# Sheet1_xbreak-k.net
KiCad netlist of a schematic drawn in Altium Designer
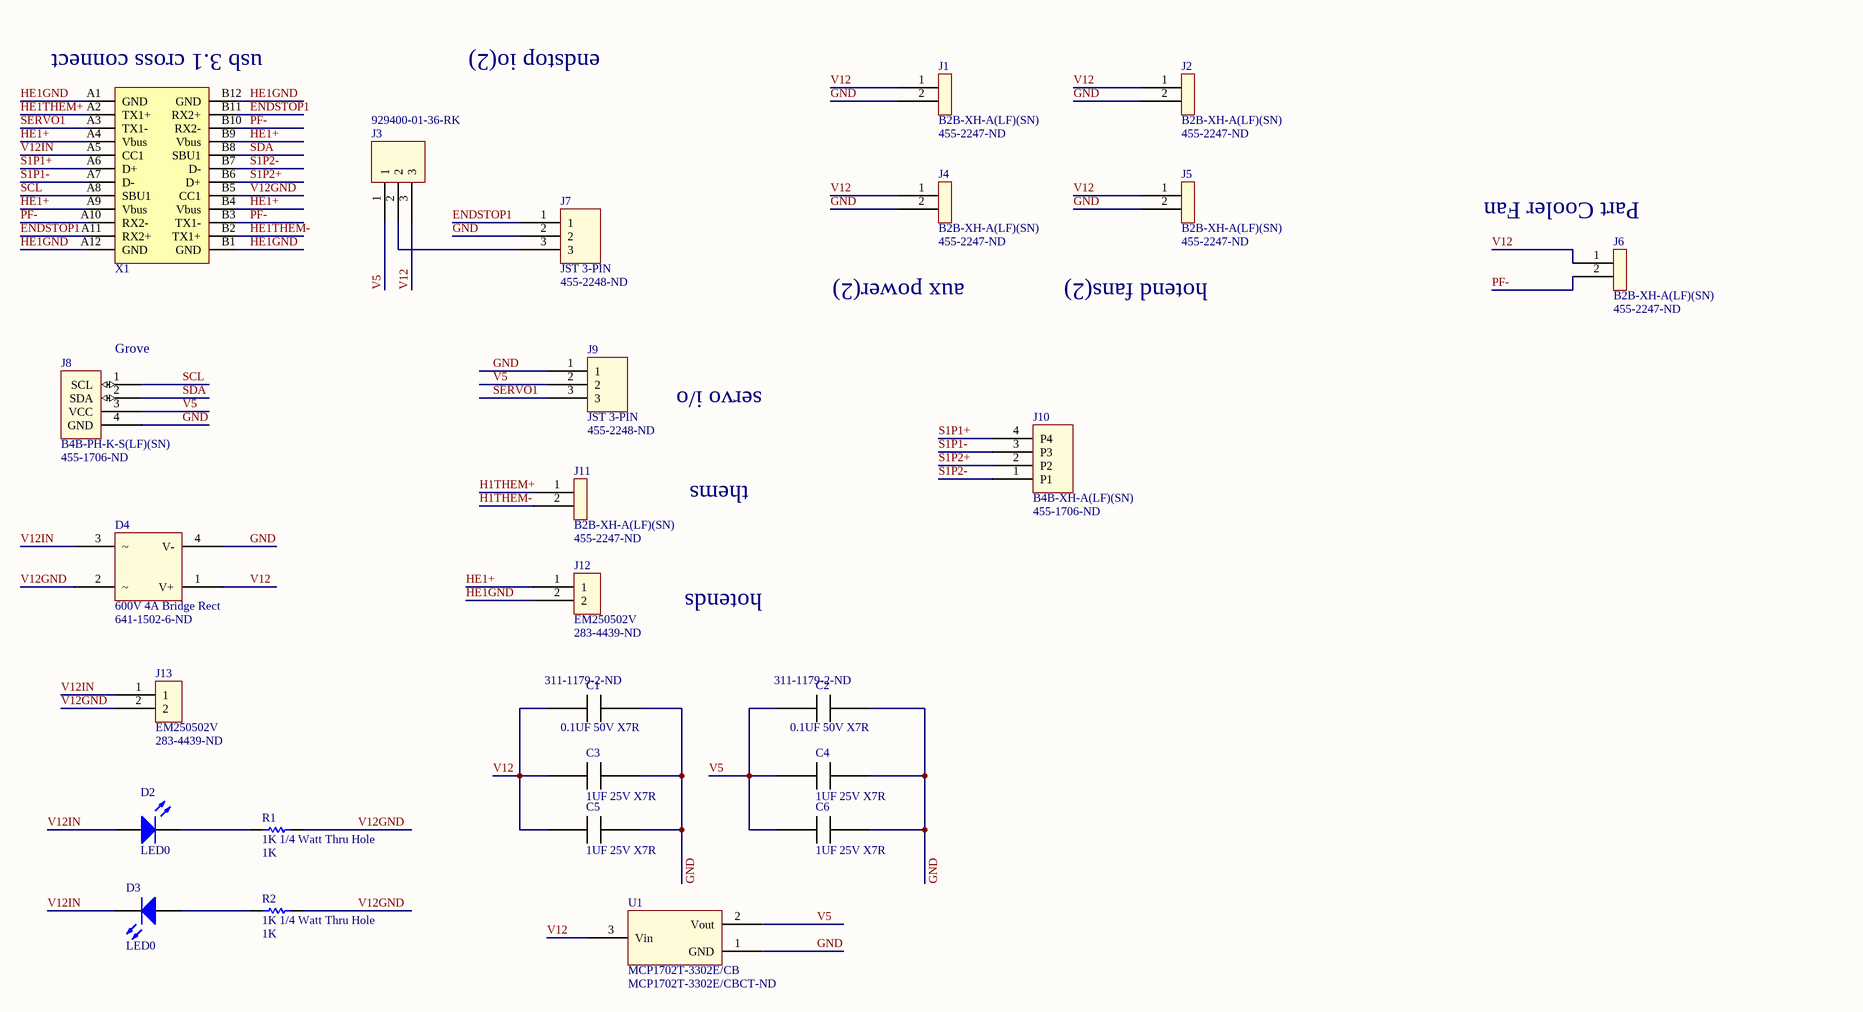
[diagram p0: Sheet1_xbreak-k.SchDoc]

(export (version "E")
  (design (tool "Eeschema 10.0.6"))
  (components
    (comp (ref "C1")
      (value "0.1UF 50V X7R")
      (footprint "C1206YageoX7R")
      (description "CAP CER 0.1UF 50V X7R 1206 YAGEO CC1206KRX7R9BB104")
      (fields (field (name "SUPPLIER PART NUMBER 1") "311-1179-2-ND"))
      (libsource (lib "servo") (part "CC1206KRX7R9BB104"))
    )
    (comp (ref "C2")
      (value "0.1UF 50V X7R")
      (footprint "C1206YageoX7R")
      (description "CAP CER 0.1UF 50V X7R 1206 YAGEO CC1206KRX7R9BB104")
      (fields (field (name "SUPPLIER PART NUMBER 1") "311-1179-2-ND"))
      (libsource (lib "servo") (part "CC1206KRX7R9BB104"))
    )
    (comp (ref "C3")
      (value "1UF 25V X7R")
      (footprint "C1206YageoX7R")
      (description "CAP CER 1UF 25V X7R 1206 Yageo CC1206KKX7R8BB105")
      (libsource (lib "servo") (part "CC1206KKX7R8BB105"))
    )
    (comp (ref "C4")
      (value "1UF 25V X7R")
      (footprint "C1206YageoX7R")
      (description "CAP CER 1UF 25V X7R 1206 Yageo CC1206KKX7R8BB105")
      (libsource (lib "servo") (part "CC1206KKX7R8BB105"))
    )
    (comp (ref "C5")
      (value "1UF 25V X7R")
      (footprint "C1206YageoX7R")
      (description "CAP CER 1UF 25V X7R 1206 Yageo CC1206KKX7R8BB105")
      (libsource (lib "servo") (part "CC1206KKX7R8BB105"))
    )
    (comp (ref "C6")
      (value "1UF 25V X7R")
      (footprint "C1206YageoX7R")
      (description "CAP CER 1UF 25V X7R 1206 Yageo CC1206KKX7R8BB105")
      (libsource (lib "servo") (part "CC1206KKX7R8BB105"))
    )
    (comp (ref "D2")
      (value "LED0")
      (footprint "LED-0")
      (description "Typical INFRARED GaAs LED")
      (fields (field (name "PUBLISHER") "Altium Limited"))
      (libsource (lib "Miscellaneous Devices") (part "LED0"))
    )
    (comp (ref "D3")
      (value "LED0")
      (footprint "LED-0")
      (description "Typical INFRARED GaAs LED")
      (fields (field (name "PUBLISHER") "Altium Limited"))
      (libsource (lib "Miscellaneous Devices") (part "LED0"))
    )
    (comp (ref "D4")
      (value "600V 4A Bridge Rect")
      (footprint "Z4DGP406L-HF")
      (description "RECT BRIDGE GP 600V 4A Z4-D ComChip Z4DGP406L-HF")
      (fields (field (name "SUPPLIER PART NUMBER 1") "641-1502-6-ND"))
      (libsource (lib "xbreak") (part "Z4DGP406L-HF"))
    )
    (comp (ref "J1")
      (value "B2B-XH-A(LF)(SN)")
      (footprint "77311-118-02LF")
      (description "CONN HEADER XH TOP 2POS 2.5MM  JST B2B-XH-A(LF)(SN)")
      (fields (field (name "SUPPLIER PART NUMBER 1") "455-2247-ND"))
      (libsource (lib "xbreak") (part "B2B-XH-A(LF)(SN)"))
    )
    (comp (ref "J2")
      (value "B2B-XH-A(LF)(SN)")
      (footprint "77311-118-02LF")
      (description "CONN HEADER XH TOP 2POS 2.5MM  JST B2B-XH-A(LF)(SN)")
      (fields (field (name "SUPPLIER PART NUMBER 1") "455-2247-ND"))
      (libsource (lib "xbreak") (part "B2B-XH-A(LF)(SN)"))
    )
    (comp (ref "J3")
      (value "929400-01-36-RK")
      (footprint "929400-01-36-RK")
      (description "3M 929400-01-36-RK CONN HEADER .100 SNGL STR 36POS - Use 3 Pin")
      (libsource (lib "xbreak") (part "929400-01-36-RK"))
    )
    (comp (ref "J4")
      (value "B2B-XH-A(LF)(SN)")
      (footprint "77311-118-02LF")
      (description "CONN HEADER XH TOP 2POS 2.5MM  JST B2B-XH-A(LF)(SN)")
      (fields (field (name "SUPPLIER PART NUMBER 1") "455-2247-ND"))
      (libsource (lib "xbreak") (part "B2B-XH-A(LF)(SN)"))
    )
    (comp (ref "J5")
      (value "B2B-XH-A(LF)(SN)")
      (footprint "77311-118-02LF")
      (description "CONN HEADER XH TOP 2POS 2.5MM  JST B2B-XH-A(LF)(SN)")
      (fields (field (name "SUPPLIER PART NUMBER 1") "455-2247-ND"))
      (libsource (lib "xbreak") (part "B2B-XH-A(LF)(SN)"))
    )
    (comp (ref "J6")
      (value "B2B-XH-A(LF)(SN)")
      (footprint "77311-118-02LF")
      (description "CONN HEADER XH TOP 2POS 2.5MM  JST B2B-XH-A(LF)(SN)")
      (fields (field (name "SUPPLIER PART NUMBER 1") "455-2247-ND"))
      (libsource (lib "xbreak") (part "B2B-XH-A(LF)(SN)"))
    )
    (comp (ref "J7")
      (value "JST 3-PIN")
      (footprint "B3B-XH-A(LF)(SN)")
      (description "CONN HEADER XH TOP 3POS 2.5MM JST B3B-XH-A(LF)(SN)")
      (fields (field (name "SUPPLIER PART NUMBER 1") "455-2248-ND"))
      (libsource (lib "xbreak") (part "B3B-XH-A(LF)(SN)"))
    )
    (comp (ref "J8")
      (value "B4B-PH-K-S(LF)(SN)")
      (footprint "B4B-PH-K-S(LF)(SN)")
      (fields (field (name "SUPPLIER PART NUMBER 1") "455-1706-ND"))
      (libsource (lib "servo") (part "B4B-PH-K-S(LF)(SN)"))
    )
    (comp (ref "J9")
      (value "JST 3-PIN")
      (footprint "B3B-XH-A(LF)(SN)")
      (description "CONN HEADER XH TOP 3POS 2.5MM JST B3B-XH-A(LF)(SN)")
      (fields (field (name "SUPPLIER PART NUMBER 1") "455-2248-ND"))
      (libsource (lib "xbreak") (part "B3B-XH-A(LF)(SN)"))
    )
    (comp (ref "J10")
      (value "B4B-XH-A(LF)(SN)")
      (footprint "B4B-PH-K-S(LF)(SN)")
      (description "CONN HEADER XH TOP 4POS 2.5MM JST B4B-XH-A(LF)(SN)")
      (fields (field (name "SUPPLIER PART NUMBER 1") "455-1706-ND"))
      (libsource (lib "xbreak") (part "B4B-XH-A(LF)(SN)"))
    )
    (comp (ref "J11")
      (value "B2B-XH-A(LF)(SN)")
      (footprint "77311-118-02LF")
      (description "CONN HEADER XH TOP 2POS 2.5MM  JST B2B-XH-A(LF)(SN)")
      (fields (field (name "SUPPLIER PART NUMBER 1") "455-2247-ND"))
      (libsource (lib "xbreak") (part "B2B-XH-A(LF)(SN)"))
    )
    (comp (ref "J12")
      (value "EM250502V")
      (footprint "EM250502V")
      (description "TERM BLOCK 16A 300V 12-26AWG Eaton Bussman EM250502V")
      (fields (field (name "SUPPLIER PART NUMBER 1") "283-4439-ND"))
      (libsource (lib "xbreak") (part "EM250502V"))
    )
    (comp (ref "J13")
      (value "EM250502V")
      (footprint "EM250502V")
      (description "TERM BLOCK 16A 300V 12-26AWG Eaton Bussman EM250502V")
      (fields (field (name "SUPPLIER PART NUMBER 1") "283-4439-ND"))
      (libsource (lib "xbreak") (part "EM250502V"))
    )
    (comp (ref "R1")
      (value "1K 1/4 Watt Thru Hole")
      (footprint "AXIAL-0.3")
      (description "Resistor")
      (fields (field (name "ALTIUM_VALUE") "1K") (field (name "PUBLISHER") "Altium Limited"))
      (libsource (lib "Miscellaneous Devices") (part "Res1"))
    )
    (comp (ref "R2")
      (value "1K 1/4 Watt Thru Hole")
      (footprint "AXIAL-0.3")
      (description "Resistor")
      (fields (field (name "ALTIUM_VALUE") "1K") (field (name "PUBLISHER") "Altium Limited"))
      (libsource (lib "Miscellaneous Devices") (part "Res1"))
    )
    (comp (ref "U1")
      (value "MCP1702T-3302E/CB")
      (footprint "MCP1702-SOT-23A")
      (description "IC REG LDO 3.3V 0.25A SOT23A-3 Microchip MCP1702T-3302E/CB")
      (fields (field (name "SUPPLIER PART NUMBER 1") "MCP1702T-3302E/CBCT-ND"))
      (libsource (lib "servo") (part "MCP1702"))
    )
    (comp (ref "X1")
      (value "USB_3_1")
      (footprint "USB_3.1")
      (description "USB 3.1 Connector")
      (fields
        (field (name "MANUFACTURER") "Amphenol Commercial Products")
        (field (name "MANUFACTURER PART NUMBER") "12401548E4#2A")
      )
      (libsource (lib "Schlib2") (part "USB 3.1"))
    )
  )
  (nets
    (net (code "1") (name "/ENDSTOP1") (class "Default")
      (node (ref "J7") (pin "1") (pinfunction "1_1") (pintype "passive"))
      (node (ref "X1") (pin "A11") (pinfunction "RX2+_A11") (pintype "passive"))
      (node (ref "X1") (pin "B11") (pinfunction "RX2+_B11") (pintype "passive"))
    )
    (net (code "2") (name "/GND") (class "Default")
      (node (ref "C1") (pin "2") (pintype "passive"))
      (node (ref "C2") (pin "2") (pintype "passive"))
      (node (ref "C3") (pin "2") (pintype "passive"))
      (node (ref "C4") (pin "2") (pintype "passive"))
      (node (ref "C5") (pin "2") (pintype "passive"))
      (node (ref "C6") (pin "2") (pintype "passive"))
      (node (ref "D4") (pin "4") (pinfunction "V-_4") (pintype "passive"))
      (node (ref "J1") (pin "2") (pintype "passive"))
      (node (ref "J2") (pin "2") (pintype "passive"))
      (node (ref "J4") (pin "2") (pintype "passive"))
      (node (ref "J5") (pin "2") (pintype "passive"))
      (node (ref "J7") (pin "2") (pinfunction "2_2") (pintype "passive"))
      (node (ref "J8") (pin "4") (pinfunction "GND_4") (pintype "power_in"))
      (node (ref "J9") (pin "1") (pinfunction "1_1") (pintype "passive"))
      (node (ref "U1") (pin "1") (pinfunction "GND_1") (pintype "power_in"))
    )
    (net (code "3") (name "/H1THEM+") (class "Default") (node (ref "J11") (pin "1") (pintype "passive")))
    (net (code "4") (name "/H1THEM-") (class "Default") (node (ref "J11") (pin "2") (pintype "passive")))
    (net (code "5") (name "/HE1+") (class "Default")
      (node (ref "J12") (pin "1") (pinfunction "1_1") (pintype "passive"))
      (node (ref "X1") (pin "A4") (pinfunction "Vbus_A4") (pintype "passive"))
      (node (ref "X1") (pin "A9") (pinfunction "Vbus_A9") (pintype "passive"))
      (node (ref "X1") (pin "B4") (pinfunction "Vbus_B4") (pintype "passive"))
      (node (ref "X1") (pin "B9") (pinfunction "Vbus_B9") (pintype "passive"))
    )
    (net (code "6") (name "/HE1GND") (class "Default")
      (node (ref "J12") (pin "2") (pinfunction "2_2") (pintype "passive"))
      (node (ref "X1") (pin "A1") (pinfunction "GND_A1") (pintype "passive"))
      (node (ref "X1") (pin "A12") (pinfunction "GND_A12") (pintype "passive"))
      (node (ref "X1") (pin "B1") (pinfunction "GND_B1") (pintype "passive"))
      (node (ref "X1") (pin "B12") (pinfunction "GND_B12") (pintype "passive"))
    )
    (net (code "7") (name "/HE1THEM+") (class "Default")
      (node (ref "X1") (pin "A2") (pinfunction "TX1+_A2") (pintype "passive"))
    )
    (net (code "8") (name "/HE1THEM-") (class "Default")
      (node (ref "X1") (pin "B2") (pinfunction "TX1+_B2") (pintype "passive"))
    )
    (net (code "9") (name "/PF-") (class "Default")
      (node (ref "J6") (pin "2") (pintype "passive"))
      (node (ref "X1") (pin "A10") (pinfunction "RX2-_A10") (pintype "passive"))
      (node (ref "X1") (pin "B10") (pinfunction "RX2-_B10") (pintype "passive"))
      (node (ref "X1") (pin "B3") (pinfunction "TX1-_B3") (pintype "passive"))
    )
    (net (code "10") (name "/S1P1+") (class "Default")
      (node (ref "J10") (pin "4") (pinfunction "P4_4") (pintype "passive"))
      (node (ref "X1") (pin "A6") (pinfunction "D+_A6") (pintype "passive"))
    )
    (net (code "11") (name "/S1P1-") (class "Default")
      (node (ref "J10") (pin "3") (pinfunction "P3_3") (pintype "passive"))
      (node (ref "X1") (pin "A7") (pinfunction "D-_A7") (pintype "passive"))
    )
    (net (code "12") (name "/S1P2+") (class "Default")
      (node (ref "J10") (pin "2") (pinfunction "P2_2") (pintype "passive"))
      (node (ref "X1") (pin "B6") (pinfunction "D+_B6") (pintype "passive"))
    )
    (net (code "13") (name "/S1P2-") (class "Default")
      (node (ref "J10") (pin "1") (pinfunction "P1_1") (pintype "passive"))
      (node (ref "X1") (pin "B7") (pinfunction "D-_B7") (pintype "passive"))
    )
    (net (code "14") (name "/SCL") (class "Default")
      (node (ref "J8") (pin "1") (pinfunction "SCL_1") (pintype "bidirectional"))
      (node (ref "X1") (pin "A8") (pinfunction "SBU1_A8") (pintype "passive"))
    )
    (net (code "15") (name "/SDA") (class "Default")
      (node (ref "J8") (pin "2") (pinfunction "SDA_2") (pintype "bidirectional"))
      (node (ref "X1") (pin "B8") (pinfunction "SBU1_B8") (pintype "passive"))
    )
    (net (code "16") (name "/SERVO1") (class "Default")
      (node (ref "J9") (pin "3") (pinfunction "3_3") (pintype "passive"))
      (node (ref "X1") (pin "A3") (pinfunction "TX1-_A3") (pintype "passive"))
    )
    (net (code "17") (name "/V5") (class "Default")
      (node (ref "C2") (pin "1") (pintype "passive"))
      (node (ref "C4") (pin "1") (pintype "passive"))
      (node (ref "C6") (pin "1") (pintype "passive"))
      (node (ref "J3") (pin "1") (pinfunction "1_1") (pintype "passive"))
      (node (ref "J8") (pin "3") (pinfunction "VCC_3") (pintype "power_in"))
      (node (ref "J9") (pin "2") (pinfunction "2_2") (pintype "passive"))
      (node (ref "U1") (pin "2") (pinfunction "Vout_2") (pintype "power_in"))
    )
    (net (code "18") (name "/V12") (class "Default")
      (node (ref "C1") (pin "1") (pintype "passive"))
      (node (ref "C3") (pin "1") (pintype "passive"))
      (node (ref "C5") (pin "1") (pintype "passive"))
      (node (ref "D4") (pin "1") (pinfunction "V+_1") (pintype "passive"))
      (node (ref "J1") (pin "1") (pintype "passive"))
      (node (ref "J2") (pin "1") (pintype "passive"))
      (node (ref "J3") (pin "3") (pinfunction "3_3") (pintype "passive"))
      (node (ref "J4") (pin "1") (pintype "passive"))
      (node (ref "J5") (pin "1") (pintype "passive"))
      (node (ref "J6") (pin "1") (pintype "passive"))
      (node (ref "U1") (pin "3") (pinfunction "Vin_3") (pintype "power_in"))
    )
    (net (code "19") (name "/V12GND") (class "Default")
      (node (ref "D4") (pin "2") (pinfunction "~_2") (pintype "passive"))
      (node (ref "J13") (pin "2") (pinfunction "2_2") (pintype "passive"))
      (node (ref "R1") (pin "2") (pinfunction "2_2") (pintype "passive"))
      (node (ref "R2") (pin "2") (pinfunction "2_2") (pintype "passive"))
      (node (ref "X1") (pin "B5") (pinfunction "CC1_B5") (pintype "passive"))
    )
    (net (code "20") (name "/V12IN") (class "Default")
      (node (ref "D2") (pin "1") (pinfunction "A_1") (pintype "passive"))
      (node (ref "D3") (pin "2") (pinfunction "K_2") (pintype "passive"))
      (node (ref "D4") (pin "3") (pinfunction "~_3") (pintype "passive"))
      (node (ref "J13") (pin "1") (pinfunction "1_1") (pintype "passive"))
      (node (ref "X1") (pin "A5") (pinfunction "CC1_A5") (pintype "passive"))
    )
    (net (code "21") (name "Net-(D2-K)") (class "Default")
      (node (ref "D2") (pin "2") (pinfunction "K_2") (pintype "passive"))
      (node (ref "R1") (pin "1") (pinfunction "1_1") (pintype "passive"))
    )
    (net (code "22") (name "Net-(D3-A)") (class "Default")
      (node (ref "D3") (pin "1") (pinfunction "A_1") (pintype "passive"))
      (node (ref "R2") (pin "1") (pinfunction "1_1") (pintype "passive"))
    )
    (net (code "23") (name "Net-(J3-Pad2)") (class "Default")
      (node (ref "J3") (pin "2") (pinfunction "2_2") (pintype "passive"))
      (node (ref "J7") (pin "3") (pinfunction "3_3") (pintype "passive"))
    )
  )
)
